# LORA.net
KiCad netlist of a schematic drawn in Altium Designer
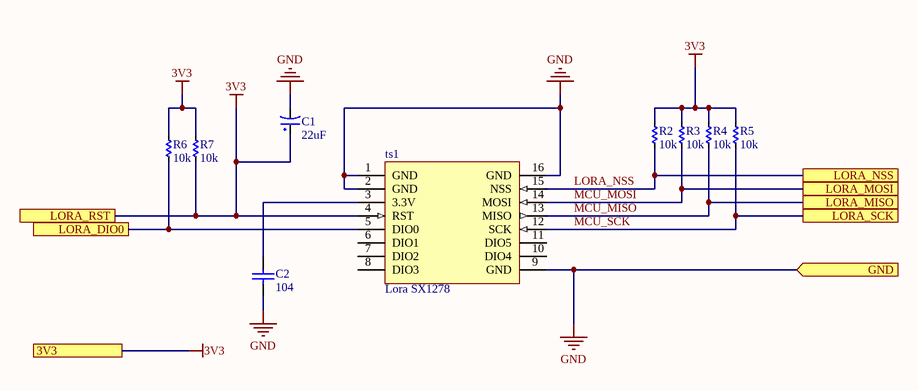
[diagram p0: LORA.SchDoc]

(export (version "E")
  (design (tool "Eeschema 10.0.6"))
  (components
    (comp (ref "C1")
      (value "22uF")
      (footprint "tu hoa 5mm")
      (description "Cắm")
      (libsource (lib "khue") (part "Tu Hoa 22uF 35V 5x11"))
    )
    (comp (ref "C2")
      (value "104")
      (footprint "tu 0805")
      (description "Dán")
      (libsource (lib "khue") (part "Tu 0805 104 50V 10%"))
    )
    (comp (ref "R2")
      (value "10k")
      (footprint "RES-SMD-0805")
      (description "Resistor")
      (fields
        (field (name "MANUFACTURER") "Generic Components")
        (field (name "PUBLISHER") "Altium Hobart Technology Centre")
      )
      (libsource (lib "LIBRARY") (part "Res-SMD"))
    )
    (comp (ref "R3")
      (value "10k")
      (footprint "RES-SMD-0805")
      (description "Resistor")
      (fields
        (field (name "MANUFACTURER") "Generic Components")
        (field (name "PUBLISHER") "Altium Hobart Technology Centre")
      )
      (libsource (lib "LIBRARY") (part "Res-SMD"))
    )
    (comp (ref "R4")
      (value "10k")
      (footprint "RES-SMD-0805")
      (description "Resistor")
      (fields
        (field (name "MANUFACTURER") "Generic Components")
        (field (name "PUBLISHER") "Altium Hobart Technology Centre")
      )
      (libsource (lib "LIBRARY") (part "Res-SMD"))
    )
    (comp (ref "R5")
      (value "10k")
      (footprint "RES-SMD-0805")
      (description "Resistor")
      (fields
        (field (name "MANUFACTURER") "Generic Components")
        (field (name "PUBLISHER") "Altium Hobart Technology Centre")
      )
      (libsource (lib "LIBRARY") (part "Res-SMD"))
    )
    (comp (ref "R6")
      (value "10k")
      (footprint "RES-SMD-0805")
      (description "Resistor")
      (fields
        (field (name "MANUFACTURER") "Generic Components")
        (field (name "PUBLISHER") "Altium Hobart Technology Centre")
      )
      (libsource (lib "LIBRARY") (part "Res-SMD"))
    )
    (comp (ref "R7")
      (value "10k")
      (footprint "RES-SMD-0805")
      (description "Resistor")
      (fields
        (field (name "MANUFACTURER") "Generic Components")
        (field (name "PUBLISHER") "Altium Hobart Technology Centre")
      )
      (libsource (lib "LIBRARY") (part "Res-SMD"))
    )
    (comp (ref "ts1")
      (value "Lora SX1278")
      (footprint "*XCVR_RFM69HW-868S2")
      (libsource (lib "SensorLORA") (part "Lora SX1278"))
    )
  )
  (nets
    (net (code "1") (name "/LORA_DIO0") (class "Default")
      (node (ref "R6") (pin "2") (pinfunction "2_2") (pintype "passive"))
      (node (ref "ts1") (pin "5") (pinfunction "DIO0_5") (pintype "power_in"))
    )
    (net (code "2") (name "/LORA_NSS") (class "Default")
      (node (ref "R2") (pin "2") (pinfunction "2_2") (pintype "passive"))
      (node (ref "ts1") (pin "15") (pinfunction "NSS_15") (pintype "input"))
    )
    (net (code "3") (name "/MCU_MISO") (class "Default")
      (node (ref "R4") (pin "2") (pinfunction "2_2") (pintype "passive"))
      (node (ref "ts1") (pin "13") (pinfunction "MISO_13") (pintype "output"))
    )
    (net (code "4") (name "/MCU_MOSI") (class "Default")
      (node (ref "R3") (pin "2") (pinfunction "2_2") (pintype "passive"))
      (node (ref "ts1") (pin "14") (pinfunction "MOSI_14") (pintype "input"))
    )
    (net (code "5") (name "/MCU_SCK") (class "Default")
      (node (ref "R5") (pin "2") (pinfunction "2_2") (pintype "passive"))
      (node (ref "ts1") (pin "12") (pinfunction "SCK_12") (pintype "input"))
    )
    (net (code "6") (name "3V3") (class "Default")
      (node (ref "C1") (pin "1") (pinfunction "1_1") (pintype "passive"))
      (node (ref "R2") (pin "1") (pinfunction "1_1") (pintype "passive"))
      (node (ref "R3") (pin "1") (pinfunction "1_1") (pintype "passive"))
      (node (ref "R4") (pin "1") (pinfunction "1_1") (pintype "passive"))
      (node (ref "R5") (pin "1") (pinfunction "1_1") (pintype "passive"))
      (node (ref "R6") (pin "1") (pinfunction "1_1") (pintype "passive"))
      (node (ref "R7") (pin "1") (pinfunction "1_1") (pintype "passive"))
      (node (ref "R7") (pin "2") (pinfunction "2_2") (pintype "passive"))
      (node (ref "ts1") (pin "4") (pinfunction "RST_4") (pintype "input"))
    )
    (net (code "7") (name "GND") (class "Default")
      (node (ref "C1") (pin "2") (pinfunction "2_2") (pintype "passive"))
      (node (ref "C2") (pin "1") (pinfunction "1_1") (pintype "passive"))
      (node (ref "ts1") (pin "1") (pinfunction "GND_1") (pintype "power_in"))
      (node (ref "ts1") (pin "16") (pinfunction "GND_16") (pintype "power_in"))
      (node (ref "ts1") (pin "2") (pinfunction "GND_2") (pintype "power_in"))
      (node (ref "ts1") (pin "9") (pinfunction "GND_9") (pintype "power_in"))
    )
    (net (code "8") (name "Net-(ts1-3.3V)") (class "Default")
      (node (ref "C2") (pin "2") (pinfunction "2_2") (pintype "passive"))
      (node (ref "ts1") (pin "3") (pinfunction "3.3V_3") (pintype "power_in"))
    )
    (net (code "9") (name "unconnected-(ts1-DIO1-Pad6)") (class "Default")
      (node (ref "ts1") (pin "6") (pinfunction "DIO1_6") (pintype "open_collector"))
    )
    (net (code "10") (name "unconnected-(ts1-DIO2-Pad7)") (class "Default")
      (node (ref "ts1") (pin "7") (pinfunction "DIO2_7") (pintype "open_collector"))
    )
    (net (code "11") (name "unconnected-(ts1-DIO3-Pad8)") (class "Default")
      (node (ref "ts1") (pin "8") (pinfunction "DIO3_8") (pintype "open_collector"))
    )
    (net (code "12") (name "unconnected-(ts1-DIO4-Pad10)") (class "Default")
      (node (ref "ts1") (pin "10") (pinfunction "DIO4_10") (pintype "power_in"))
    )
    (net (code "13") (name "unconnected-(ts1-DIO5-Pad11)") (class "Default")
      (node (ref "ts1") (pin "11") (pinfunction "DIO5_11") (pintype "open_collector"))
    )
  )
)
